# Opto-coupler_hall-reciever.net
KiCad netlist of a schematic drawn in EAGLE
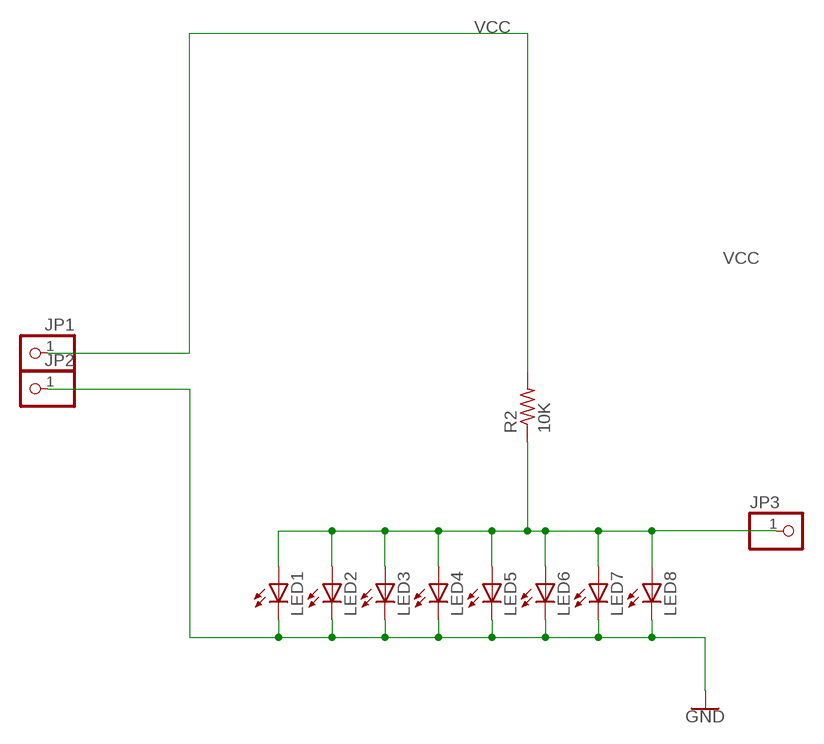
[diagram p0: schematic, sheet 1]

(export (version "E")
  (design (tool "Eeschema 10.0.6"))
  (components
    (comp (ref "JP1")
      (value "PINHD-1X1")
      (footprint "eagle-import:1X01")
      (libsource (lib "eagle-import") (part "PINHD-1X1"))
    )
    (comp (ref "JP2")
      (value "PINHD-1X1")
      (footprint "eagle-import:1X01")
      (libsource (lib "eagle-import") (part "PINHD-1X1"))
    )
    (comp (ref "JP3")
      (value "PINHD-1X1")
      (footprint "eagle-import:1X01")
      (libsource (lib "eagle-import") (part "PINHD-1X1"))
    )
    (comp (ref "LED1")
      (value "LEDCHIP-LED0603")
      (footprint "eagle-import:CHIP-LED0603")
      (libsource (lib "eagle-import") (part "LEDCHIP-LED0603"))
    )
    (comp (ref "LED2")
      (value "LEDCHIP-LED0603")
      (footprint "eagle-import:CHIP-LED0603")
      (libsource (lib "eagle-import") (part "LEDCHIP-LED0603"))
    )
    (comp (ref "LED3")
      (value "LEDCHIP-LED0603")
      (footprint "eagle-import:CHIP-LED0603")
      (libsource (lib "eagle-import") (part "LEDCHIP-LED0603"))
    )
    (comp (ref "LED4")
      (value "LEDCHIP-LED0603")
      (footprint "eagle-import:CHIP-LED0603")
      (libsource (lib "eagle-import") (part "LEDCHIP-LED0603"))
    )
    (comp (ref "LED5")
      (value "LEDCHIP-LED0603")
      (footprint "eagle-import:CHIP-LED0603")
      (libsource (lib "eagle-import") (part "LEDCHIP-LED0603"))
    )
    (comp (ref "LED6")
      (value "LEDCHIP-LED0603")
      (footprint "eagle-import:CHIP-LED0603")
      (libsource (lib "eagle-import") (part "LEDCHIP-LED0603"))
    )
    (comp (ref "LED7")
      (value "LEDCHIP-LED0603")
      (footprint "eagle-import:CHIP-LED0603")
      (libsource (lib "eagle-import") (part "LEDCHIP-LED0603"))
    )
    (comp (ref "LED8")
      (value "LEDCHIP-LED0603")
      (footprint "eagle-import:CHIP-LED0603")
      (libsource (lib "eagle-import") (part "LEDCHIP-LED0603"))
    )
    (comp (ref "R2")
      (value "10K")
      (footprint "eagle-import:R0603")
      (libsource (lib "eagle-import") (part "R-US_R0603"))
    )
  )
  (nets
    (net (code "1") (name "/VCC") (class "Default")
      (node (ref "JP1") (pin "1") (pinfunction "1_1") (pintype "passive"))
      (node (ref "R2") (pin "2") (pinfunction "2_2") (pintype "passive"))
    )
    (net (code "2") (name "GND") (class "Default")
      (node (ref "JP2") (pin "1") (pinfunction "1_1") (pintype "passive"))
      (node (ref "LED1") (pin "C") (pinfunction "C_C") (pintype "passive"))
      (node (ref "LED2") (pin "C") (pinfunction "C_C") (pintype "passive"))
      (node (ref "LED3") (pin "C") (pinfunction "C_C") (pintype "passive"))
      (node (ref "LED4") (pin "C") (pinfunction "C_C") (pintype "passive"))
      (node (ref "LED5") (pin "C") (pinfunction "C_C") (pintype "passive"))
      (node (ref "LED6") (pin "C") (pinfunction "C_C") (pintype "passive"))
      (node (ref "LED7") (pin "C") (pinfunction "C_C") (pintype "passive"))
      (node (ref "LED8") (pin "C") (pinfunction "C_C") (pintype "passive"))
    )
    (net (code "3") (name "Net-(JP3-Pad1)") (class "Default")
      (node (ref "JP3") (pin "1") (pinfunction "1_1") (pintype "passive"))
      (node (ref "LED1") (pin "A") (pinfunction "A_A") (pintype "passive"))
      (node (ref "LED2") (pin "A") (pinfunction "A_A") (pintype "passive"))
      (node (ref "LED3") (pin "A") (pinfunction "A_A") (pintype "passive"))
      (node (ref "LED4") (pin "A") (pinfunction "A_A") (pintype "passive"))
      (node (ref "LED5") (pin "A") (pinfunction "A_A") (pintype "passive"))
      (node (ref "LED6") (pin "A") (pinfunction "A_A") (pintype "passive"))
      (node (ref "LED7") (pin "A") (pinfunction "A_A") (pintype "passive"))
      (node (ref "LED8") (pin "A") (pinfunction "A_A") (pintype "passive"))
      (node (ref "R2") (pin "1") (pinfunction "1_1") (pintype "passive"))
    )
  )
)
